# 03_-_miniPCI.net
KiCad netlist of a schematic drawn in Altium Designer
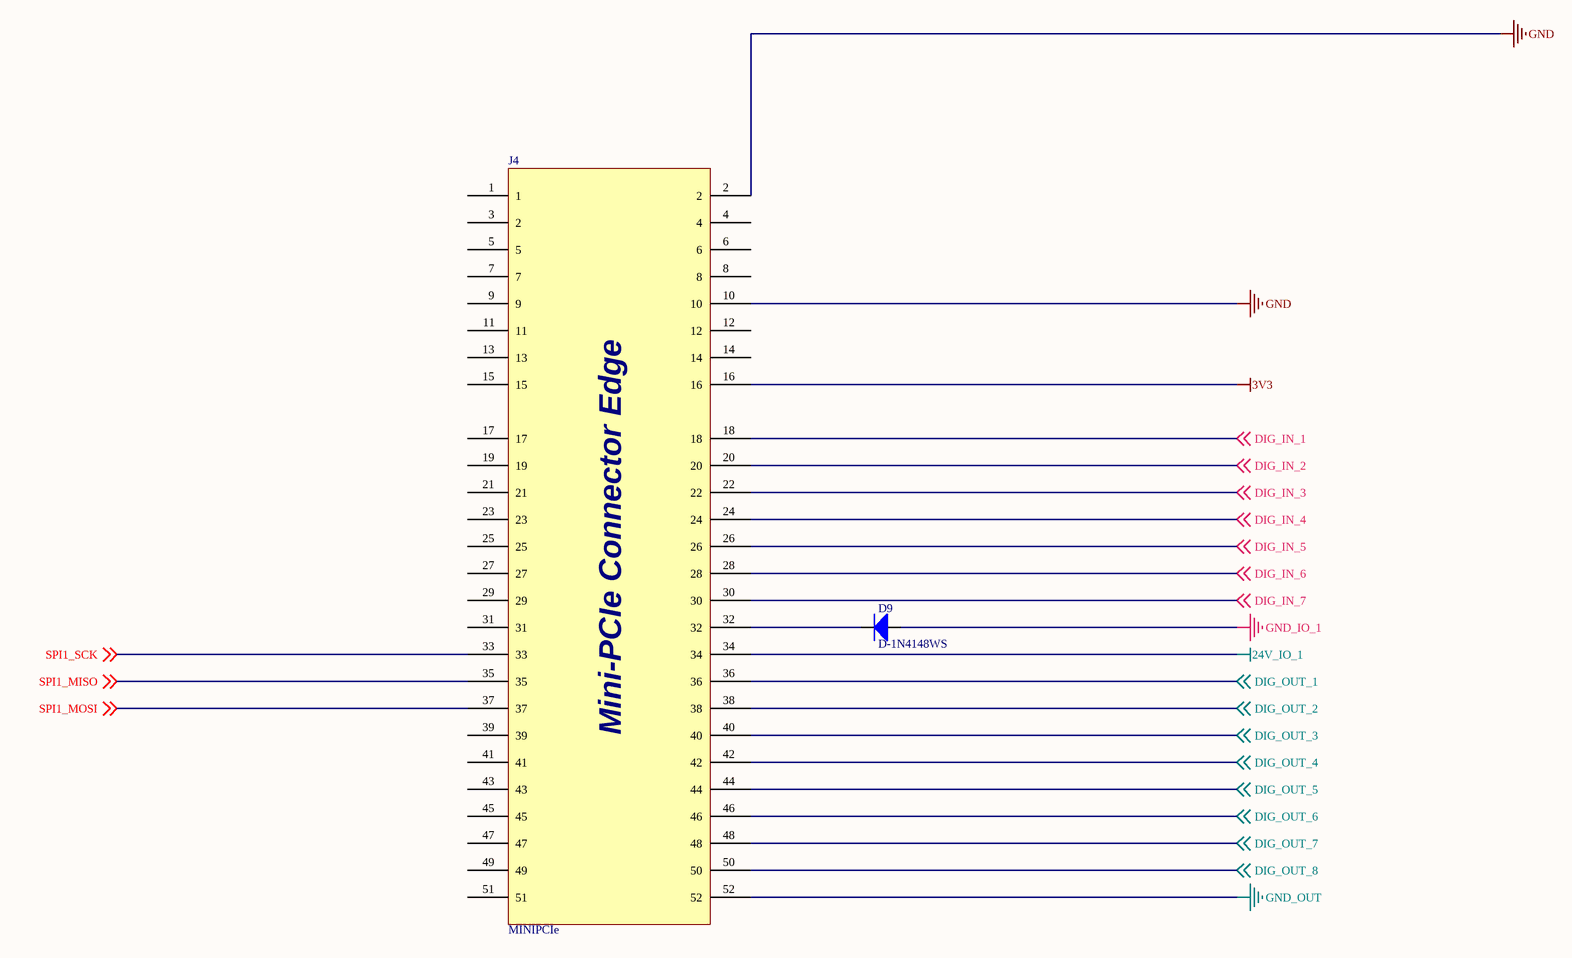
[diagram p0: [03] - miniPCI.SchDoc]

(export (version "E")
  (design (tool "Eeschema 10.0.6"))
  (components
    (comp (ref "D9")
      (value "D-1N4148WS")
      (footprint "SOD-323")
      (description "DIODES INC. - 1N4148WS-7-F - DIODE, SS SWITCH, 75V, 0.2W, SOD323")
      (fields
        (field (name "MANUFACTURER") "DIODES INC.")
        (field (name "MANUFACTURER PART NUMBER") "1N4148WS-7-F")
      )
      (libsource (lib "CPU_STM_080816") (part "D-1N4148WS"))
    )
    (comp (ref "J4")
      (value "MINIPCIe")
      (footprint "MINI PCIe")
      (libsource (lib "CPU_STM_080816") (part "MINIPCIe"))
    )
  )
  (nets
    (net (code "1") (name "3V3") (class "Default")
      (node (ref "J4") (pin "16") (pinfunction "16_16") (pintype "passive"))
    )
    (net (code "2") (name "24V_IO_1") (class "Default")
      (node (ref "J4") (pin "34") (pinfunction "34_34") (pintype "passive"))
    )
    (net (code "3") (name "DIG_IN_1") (class "Default")
      (node (ref "J4") (pin "18") (pinfunction "18_18") (pintype "passive"))
    )
    (net (code "4") (name "DIG_IN_2") (class "Default")
      (node (ref "J4") (pin "20") (pinfunction "20_20") (pintype "passive"))
    )
    (net (code "5") (name "DIG_IN_3") (class "Default")
      (node (ref "J4") (pin "22") (pinfunction "22_22") (pintype "passive"))
    )
    (net (code "6") (name "DIG_IN_4") (class "Default")
      (node (ref "J4") (pin "24") (pinfunction "24_24") (pintype "passive"))
    )
    (net (code "7") (name "DIG_IN_5") (class "Default")
      (node (ref "J4") (pin "26") (pinfunction "26_26") (pintype "passive"))
    )
    (net (code "8") (name "DIG_IN_6") (class "Default")
      (node (ref "J4") (pin "28") (pinfunction "28_28") (pintype "passive"))
    )
    (net (code "9") (name "DIG_IN_7") (class "Default")
      (node (ref "J4") (pin "30") (pinfunction "30_30") (pintype "passive"))
    )
    (net (code "10") (name "DIG_OUT_1") (class "Default")
      (node (ref "J4") (pin "36") (pinfunction "36_36") (pintype "passive"))
    )
    (net (code "11") (name "DIG_OUT_2") (class "Default")
      (node (ref "J4") (pin "38") (pinfunction "38_38") (pintype "passive"))
    )
    (net (code "12") (name "DIG_OUT_3") (class "Default")
      (node (ref "J4") (pin "40") (pinfunction "40_40") (pintype "passive"))
    )
    (net (code "13") (name "DIG_OUT_4") (class "Default")
      (node (ref "J4") (pin "42") (pinfunction "42_42") (pintype "passive"))
    )
    (net (code "14") (name "DIG_OUT_5") (class "Default")
      (node (ref "J4") (pin "44") (pinfunction "44_44") (pintype "passive"))
    )
    (net (code "15") (name "DIG_OUT_6") (class "Default")
      (node (ref "J4") (pin "46") (pinfunction "46_46") (pintype "passive"))
    )
    (net (code "16") (name "DIG_OUT_7") (class "Default")
      (node (ref "J4") (pin "48") (pinfunction "48_48") (pintype "passive"))
    )
    (net (code "17") (name "DIG_OUT_8") (class "Default")
      (node (ref "J4") (pin "50") (pinfunction "50_50") (pintype "passive"))
    )
    (net (code "18") (name "GND") (class "Default")
      (node (ref "J4") (pin "10") (pinfunction "10_10") (pintype "passive"))
      (node (ref "J4") (pin "2") (pinfunction "2_2") (pintype "passive"))
    )
    (net (code "19") (name "GND_IO_1") (class "Default")
      (node (ref "D9") (pin "2") (pinfunction "2_2") (pintype "passive"))
    )
    (net (code "20") (name "GND_OUT") (class "Default")
      (node (ref "J4") (pin "52") (pinfunction "52_52") (pintype "passive"))
    )
    (net (code "21") (name "Net-(D9-Pad1)") (class "Default")
      (node (ref "D9") (pin "1") (pinfunction "1_1") (pintype "passive"))
      (node (ref "J4") (pin "32") (pinfunction "32_32") (pintype "passive"))
    )
    (net (code "22") (name "SPI1_MISO") (class "Default")
      (node (ref "J4") (pin "35") (pinfunction "35_35") (pintype "passive"))
    )
    (net (code "23") (name "SPI1_MOSI") (class "Default")
      (node (ref "J4") (pin "37") (pinfunction "37_37") (pintype "passive"))
    )
    (net (code "24") (name "SPI1_SCK") (class "Default")
      (node (ref "J4") (pin "33") (pinfunction "33_33") (pintype "passive"))
    )
    (net (code "25") (name "unconnected-(J4-2-Pad3)") (class "Default")
      (node (ref "J4") (pin "3") (pinfunction "2_3") (pintype "passive"))
    )
    (net (code "26") (name "unconnected-(J4-Pad1)") (class "Default")
      (node (ref "J4") (pin "1") (pinfunction "1_1") (pintype "passive"))
    )
    (net (code "27") (name "unconnected-(J4-Pad4)") (class "Default")
      (node (ref "J4") (pin "4") (pinfunction "4_4") (pintype "passive"))
    )
    (net (code "28") (name "unconnected-(J4-Pad5)") (class "Default")
      (node (ref "J4") (pin "5") (pinfunction "5_5") (pintype "passive"))
    )
    (net (code "29") (name "unconnected-(J4-Pad6)") (class "Default")
      (node (ref "J4") (pin "6") (pinfunction "6_6") (pintype "passive"))
    )
    (net (code "30") (name "unconnected-(J4-Pad7)") (class "Default")
      (node (ref "J4") (pin "7") (pinfunction "7_7") (pintype "passive"))
    )
    (net (code "31") (name "unconnected-(J4-Pad8)") (class "Default")
      (node (ref "J4") (pin "8") (pinfunction "8_8") (pintype "passive"))
    )
    (net (code "32") (name "unconnected-(J4-Pad9)") (class "Default")
      (node (ref "J4") (pin "9") (pinfunction "9_9") (pintype "passive"))
    )
    (net (code "33") (name "unconnected-(J4-Pad11)") (class "Default")
      (node (ref "J4") (pin "11") (pinfunction "11_11") (pintype "passive"))
    )
    (net (code "34") (name "unconnected-(J4-Pad12)") (class "Default")
      (node (ref "J4") (pin "12") (pinfunction "12_12") (pintype "passive"))
    )
    (net (code "35") (name "unconnected-(J4-Pad13)") (class "Default")
      (node (ref "J4") (pin "13") (pinfunction "13_13") (pintype "passive"))
    )
    (net (code "36") (name "unconnected-(J4-Pad14)") (class "Default")
      (node (ref "J4") (pin "14") (pinfunction "14_14") (pintype "passive"))
    )
    (net (code "37") (name "unconnected-(J4-Pad15)") (class "Default")
      (node (ref "J4") (pin "15") (pinfunction "15_15") (pintype "passive"))
    )
    (net (code "38") (name "unconnected-(J4-Pad17)") (class "Default")
      (node (ref "J4") (pin "17") (pinfunction "17_17") (pintype "passive"))
    )
    (net (code "39") (name "unconnected-(J4-Pad19)") (class "Default")
      (node (ref "J4") (pin "19") (pinfunction "19_19") (pintype "passive"))
    )
    (net (code "40") (name "unconnected-(J4-Pad21)") (class "Default")
      (node (ref "J4") (pin "21") (pinfunction "21_21") (pintype "passive"))
    )
    (net (code "41") (name "unconnected-(J4-Pad23)") (class "Default")
      (node (ref "J4") (pin "23") (pinfunction "23_23") (pintype "passive"))
    )
    (net (code "42") (name "unconnected-(J4-Pad25)") (class "Default")
      (node (ref "J4") (pin "25") (pinfunction "25_25") (pintype "passive"))
    )
    (net (code "43") (name "unconnected-(J4-Pad27)") (class "Default")
      (node (ref "J4") (pin "27") (pinfunction "27_27") (pintype "passive"))
    )
    (net (code "44") (name "unconnected-(J4-Pad29)") (class "Default")
      (node (ref "J4") (pin "29") (pinfunction "29_29") (pintype "passive"))
    )
    (net (code "45") (name "unconnected-(J4-Pad31)") (class "Default")
      (node (ref "J4") (pin "31") (pinfunction "31_31") (pintype "passive"))
    )
    (net (code "46") (name "unconnected-(J4-Pad39)") (class "Default")
      (node (ref "J4") (pin "39") (pinfunction "39_39") (pintype "passive"))
    )
    (net (code "47") (name "unconnected-(J4-Pad41)") (class "Default")
      (node (ref "J4") (pin "41") (pinfunction "41_41") (pintype "passive"))
    )
    (net (code "48") (name "unconnected-(J4-Pad43)") (class "Default")
      (node (ref "J4") (pin "43") (pinfunction "43_43") (pintype "passive"))
    )
    (net (code "49") (name "unconnected-(J4-Pad45)") (class "Default")
      (node (ref "J4") (pin "45") (pinfunction "45_45") (pintype "passive"))
    )
    (net (code "50") (name "unconnected-(J4-Pad47)") (class "Default")
      (node (ref "J4") (pin "47") (pinfunction "47_47") (pintype "passive"))
    )
    (net (code "51") (name "unconnected-(J4-Pad49)") (class "Default")
      (node (ref "J4") (pin "49") (pinfunction "49_49") (pintype "passive"))
    )
    (net (code "52") (name "unconnected-(J4-Pad51)") (class "Default")
      (node (ref "J4") (pin "51") (pinfunction "51_51") (pintype "passive"))
    )
  )
)
